# Yitran_IT900_Hutschiene_PIM7A_908_1_4_un.net
KiCad netlist of a schematic drawn in EAGLE
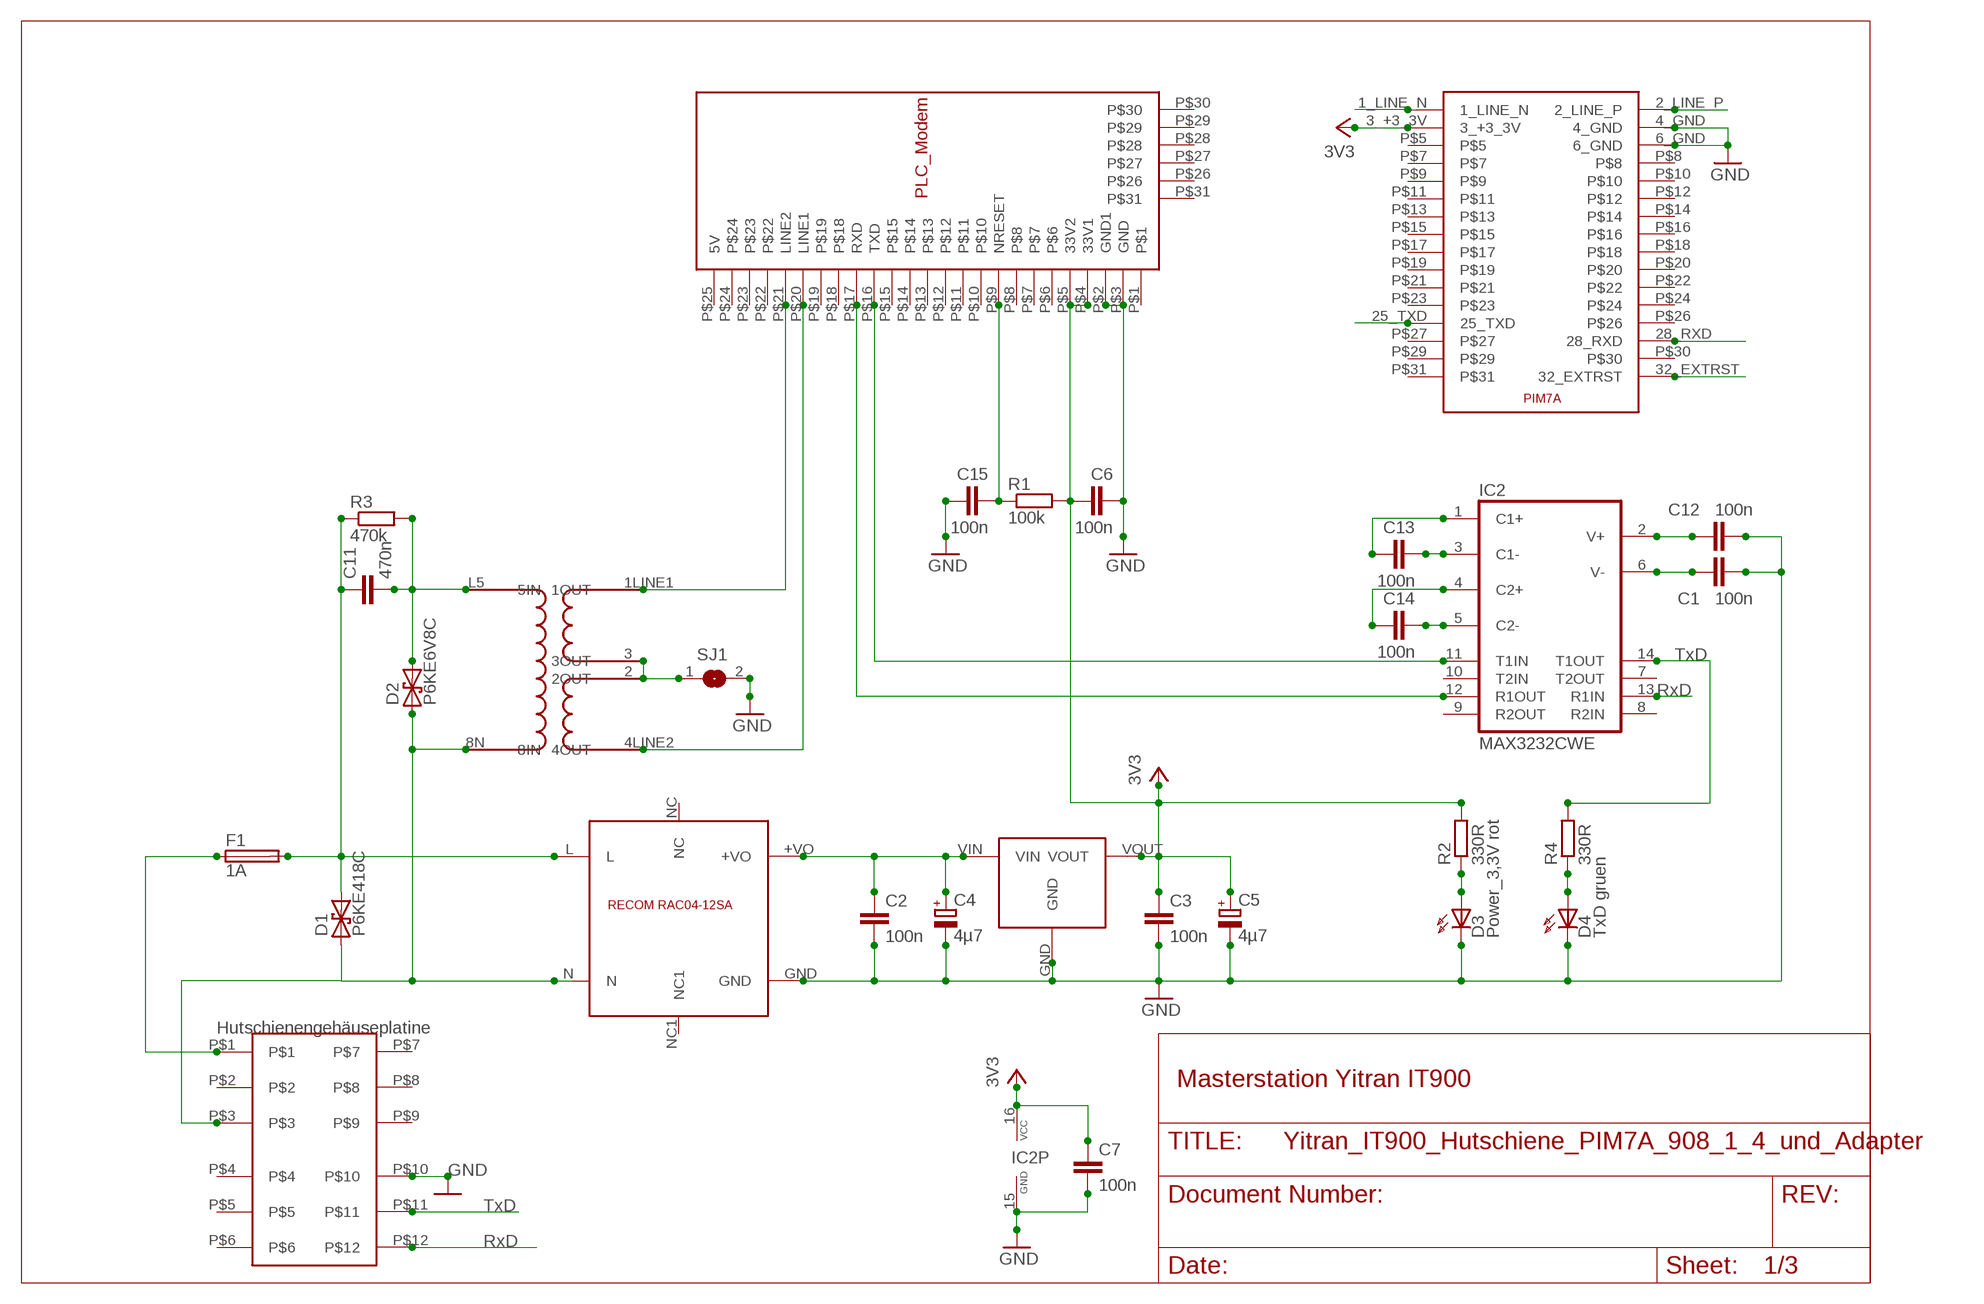
[diagram p0: schematic, sheet 1]
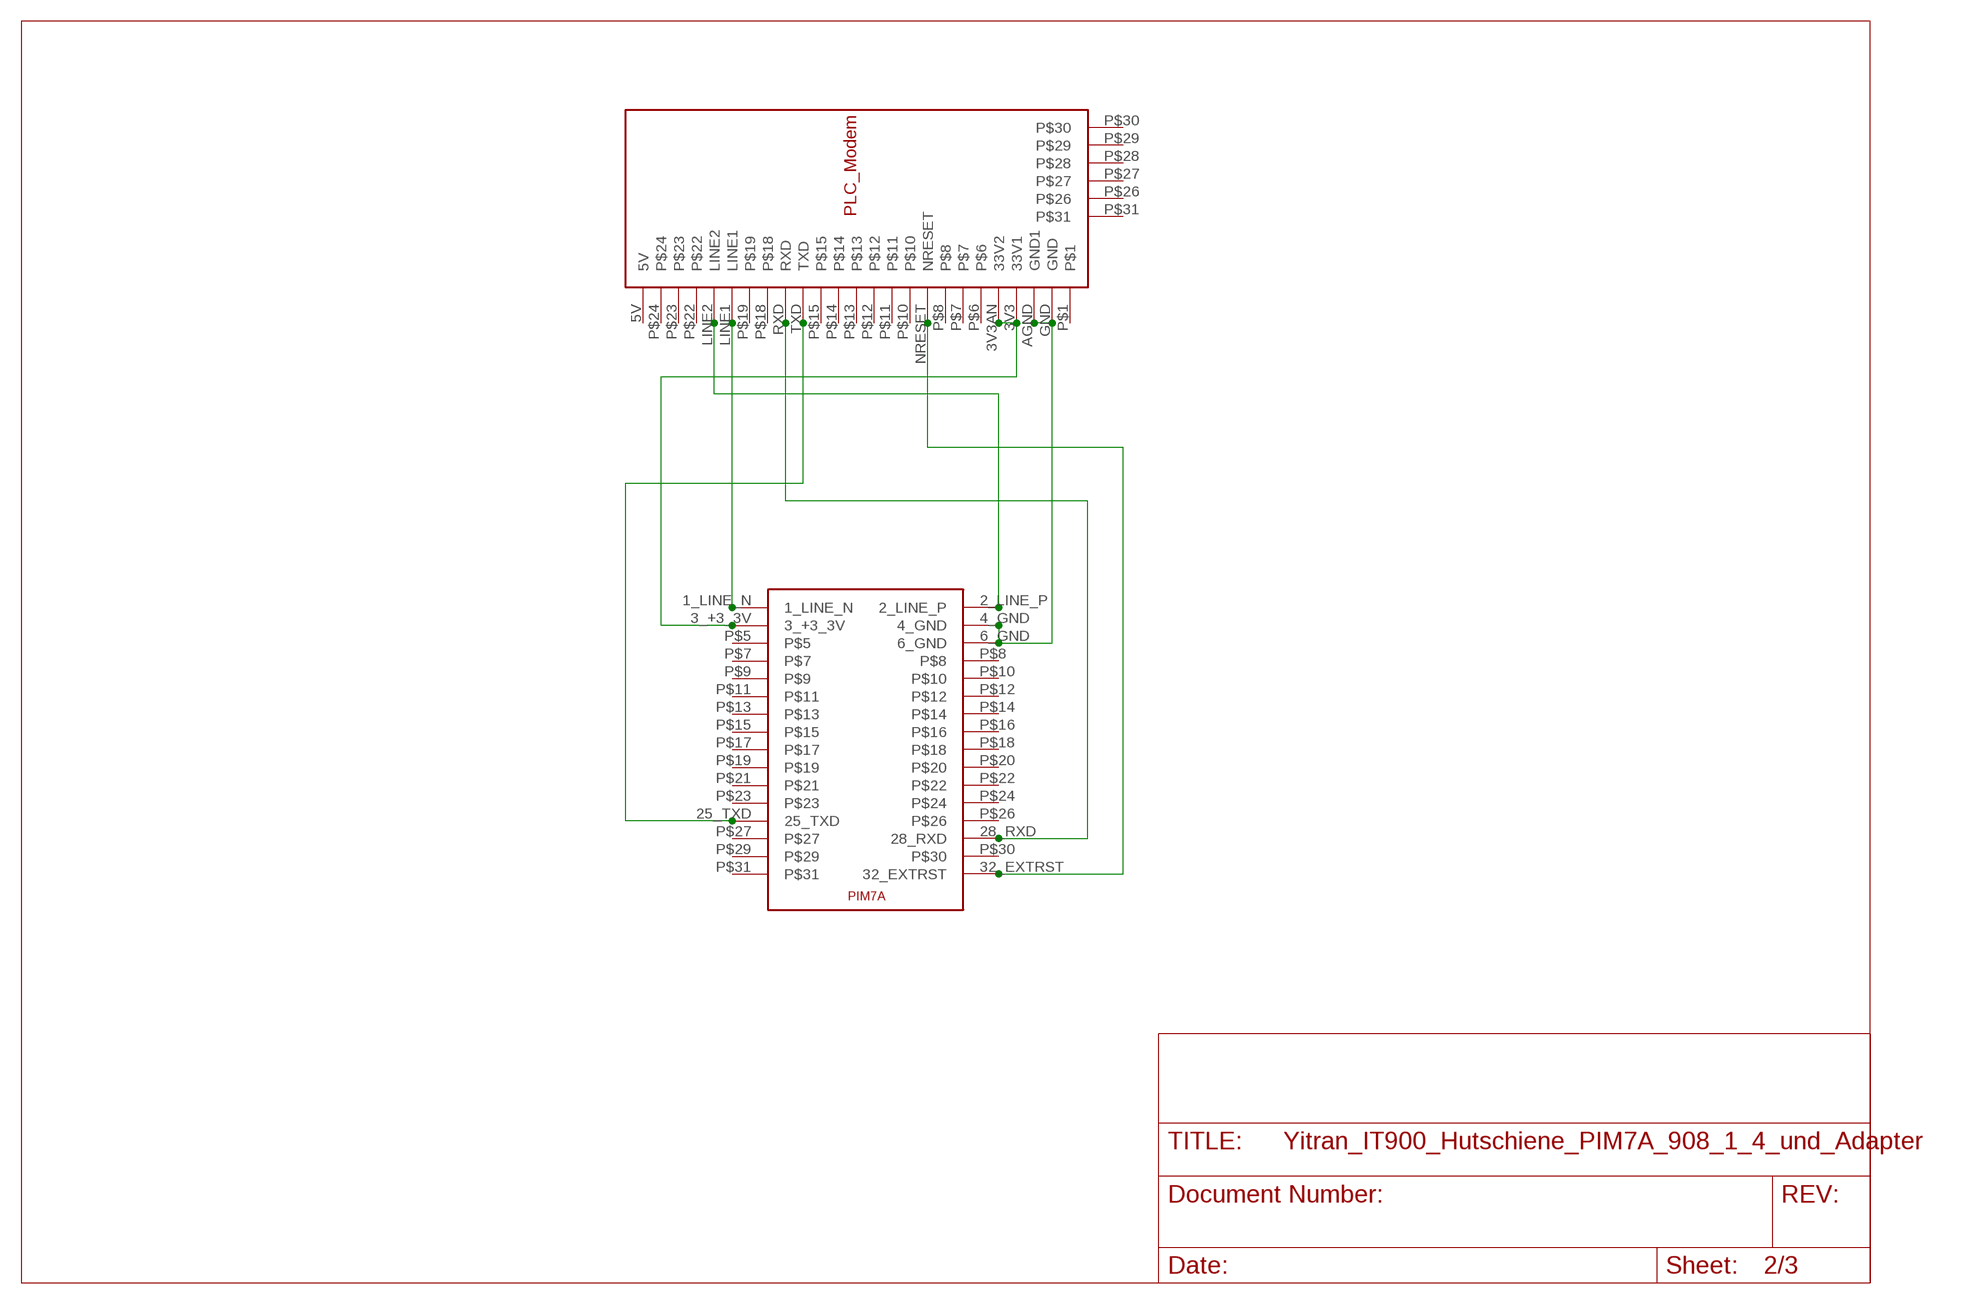
[diagram p1: schematic, sheet 2]
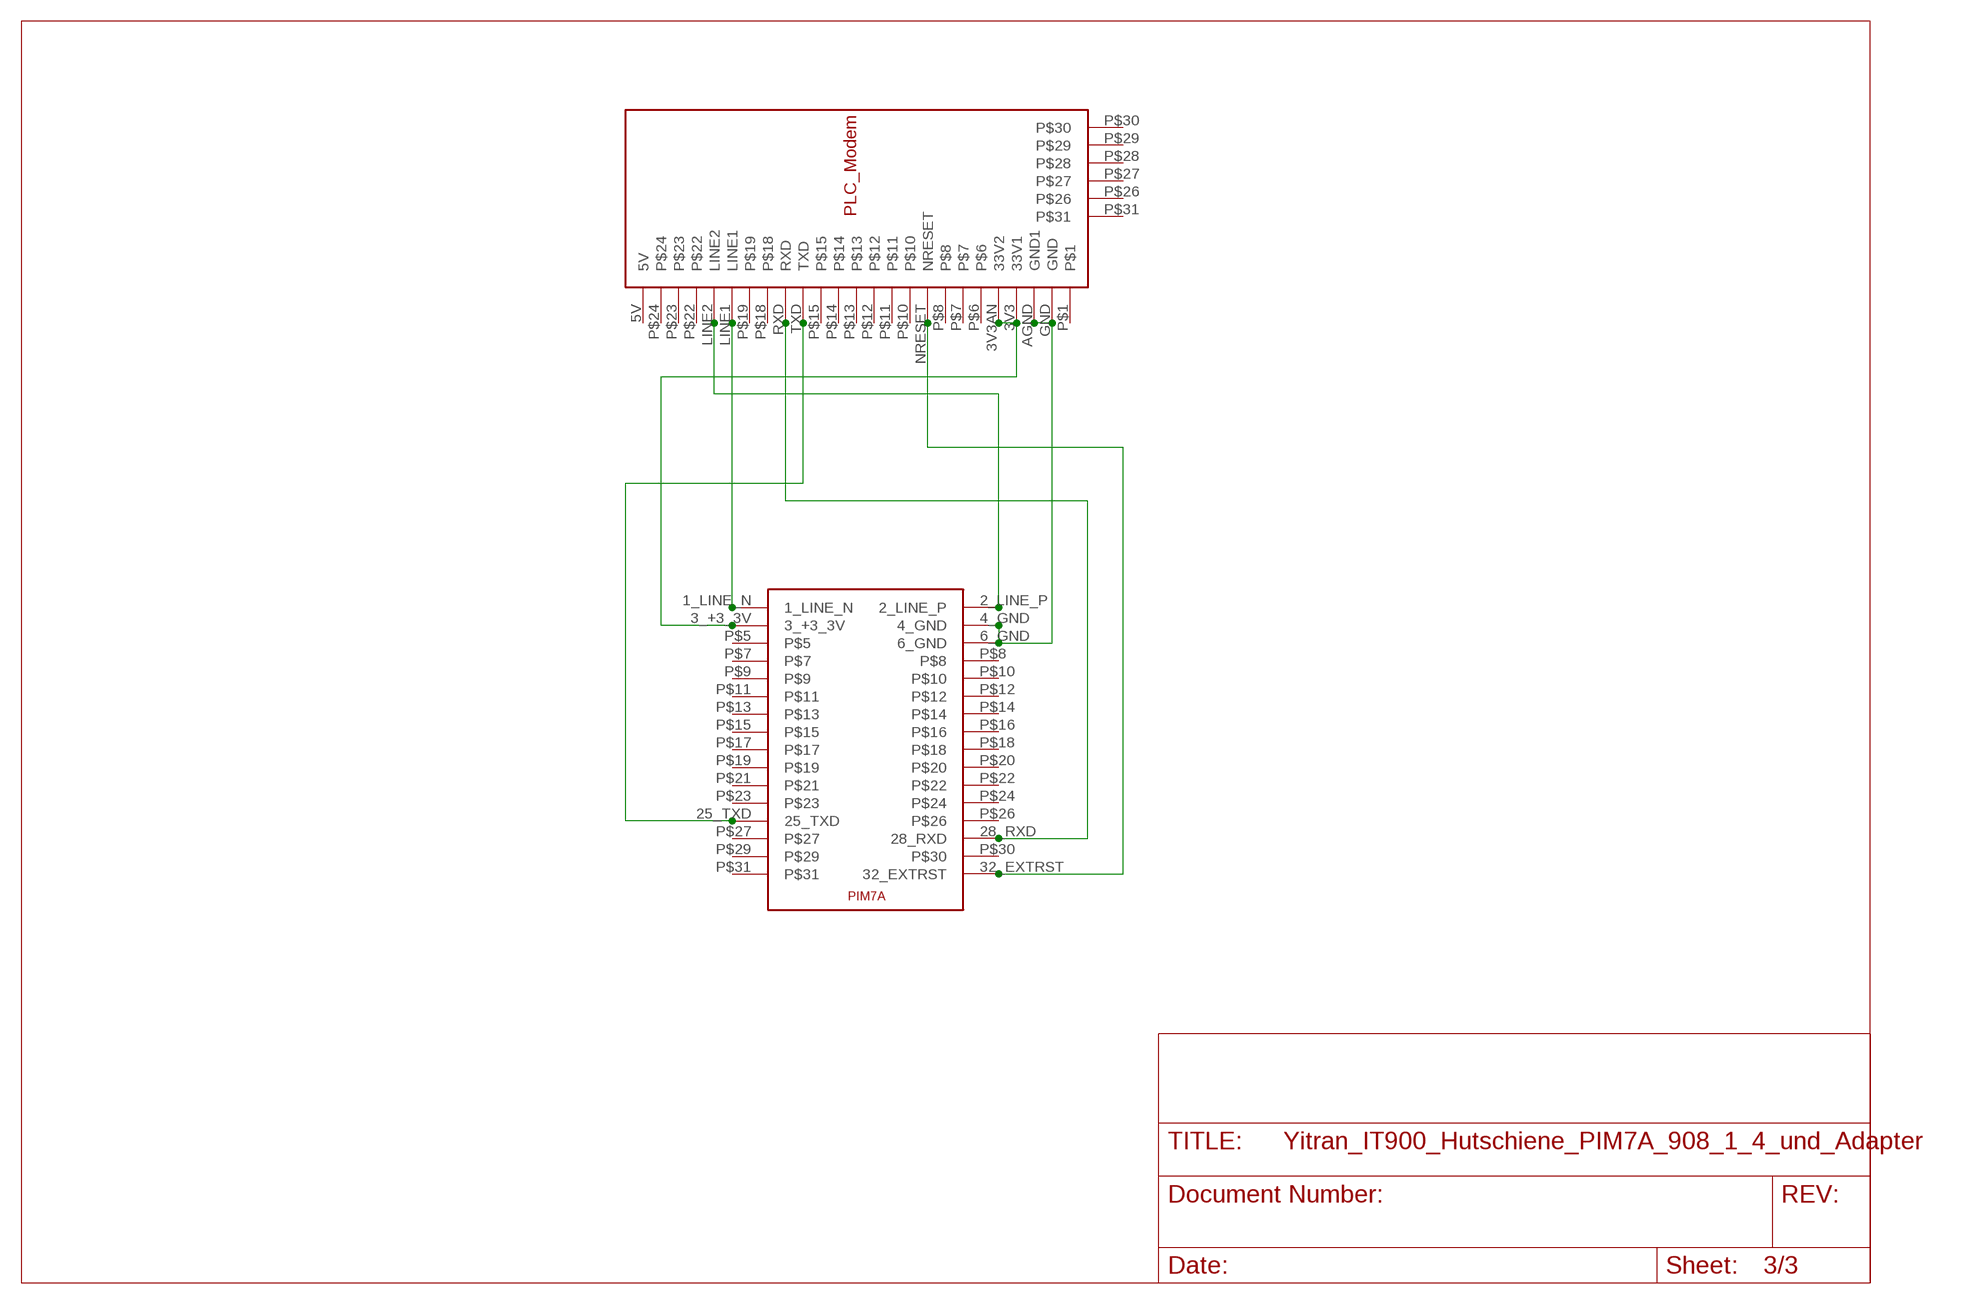
[diagram p2: schematic, sheet 3]

(export (version "E")
  (design (tool "Eeschema 10.0.6"))
  (components
    (comp (ref "U$5")
      (value "MODEMSTECKER_KLEINE_PINS")
      (footprint "eagle-import:MODEM_FUSS_KLEINE_PINS")
      (libsource (lib "eagle-import") (part "MODEMSTECKER_KLEINE_PINS"))
    )
    (comp (ref "U$6")
      (value "IT900PIM7A")
      (footprint "eagle-import:IT900PIM7A")
      (libsource (lib "eagle-import") (part "IT900PIM7A"))
    )
    (comp (ref "U$7")
      (value "MODEMSTECKER_KLEINE_PINS")
      (footprint "eagle-import:MODEM_FUSS_KLEINE_PINS")
      (libsource (lib "eagle-import") (part "MODEMSTECKER_KLEINE_PINS"))
    )
    (comp (ref "U$8")
      (value "IT900PIM7A")
      (footprint "eagle-import:IT900PIM7A")
      (libsource (lib "eagle-import") (part "IT900PIM7A"))
    )
    (comp (ref "C1")
      (value "100n")
      (footprint "eagle-import:C1206K")
      (libsource (lib "eagle-import") (part "C-EUC1206K"))
    )
    (comp (ref "C2")
      (value "100n")
      (footprint "eagle-import:C1206K")
      (libsource (lib "eagle-import") (part "C-EUC1206K"))
    )
    (comp (ref "C3")
      (value "100n")
      (footprint "eagle-import:C1206K")
      (libsource (lib "eagle-import") (part "C-EUC1206K"))
    )
    (comp (ref "C4")
      (value "4µ7")
      (footprint "eagle-import:E2,5-5")
      (libsource (lib "eagle-import") (part "CPOL-EUE2.5-5"))
    )
    (comp (ref "C5")
      (value "4µ7")
      (footprint "eagle-import:E2,5-5")
      (libsource (lib "eagle-import") (part "CPOL-EUE2.5-5"))
    )
    (comp (ref "C6")
      (value "100n")
      (footprint "eagle-import:C1206K")
      (libsource (lib "eagle-import") (part "C-EUC1206K"))
    )
    (comp (ref "C7")
      (value "100n")
      (footprint "eagle-import:C1206K")
      (libsource (lib "eagle-import") (part "C-EUC1206K"))
    )
    (comp (ref "C11")
      (value "470n")
      (footprint "eagle-import:C150-091X182")
      (libsource (lib "eagle-import") (part "C-EU150-091X182"))
    )
    (comp (ref "C12")
      (value "100n")
      (footprint "eagle-import:C1206K")
      (libsource (lib "eagle-import") (part "C-EUC1206K"))
    )
    (comp (ref "C13")
      (value "100n")
      (footprint "eagle-import:C1206K")
      (libsource (lib "eagle-import") (part "C-EUC1206K"))
    )
    (comp (ref "C14")
      (value "100n")
      (footprint "eagle-import:C1206K")
      (libsource (lib "eagle-import") (part "C-EUC1206K"))
    )
    (comp (ref "C15")
      (value "100n")
      (footprint "eagle-import:C1206K")
      (libsource (lib "eagle-import") (part "C-EUC1206K"))
    )
    (comp (ref "D1")
      (value "P6KE418C")
      (footprint "eagle-import:CB417-15")
      (libsource (lib "eagle-import") (part "P6KEXXC"))
    )
    (comp (ref "D2")
      (value "P6KE6V8C")
      (footprint "eagle-import:CB417-15")
      (libsource (lib "eagle-import") (part "P6KEXXC"))
    )
    (comp (ref "D3")
      (value "Power_3,3V rot")
      (footprint "eagle-import:HLMP6")
      (fields (field (name "MF") "AGILENT TECHNOLOGIES") (field (name "MPN") "HLMP-6500"))
      (libsource (lib "eagle-import") (part "HLMP6"))
    )
    (comp (ref "D4")
      (value "TxD gruen")
      (footprint "eagle-import:HLMP6")
      (fields (field (name "MF") "AGILENT TECHNOLOGIES") (field (name "MPN") "HLMP-6500"))
      (libsource (lib "eagle-import") (part "HLMP6"))
    )
    (comp (ref "F1")
      (value "1A")
      (footprint "eagle-import:TR5")
      (libsource (lib "eagle-import") (part "TR5"))
    )
    (comp (ref "IC2")
      (value "MAX3232CWE")
      (footprint "eagle-import:SO16L")
      (fields (field (name "MF") "MAXIM") (field (name "MPN") "MAX3232CWE+"))
      (libsource (lib "eagle-import") (part "MAX3232WEC"))
    )
    (comp (ref "R1")
      (value "100k")
      (footprint "eagle-import:M1406")
      (libsource (lib "eagle-import") (part "R-EU_M1406"))
    )
    (comp (ref "R2")
      (value "330R")
      (footprint "eagle-import:R1206")
      (libsource (lib "eagle-import") (part "R-EU_R1206"))
    )
    (comp (ref "R3")
      (value "470k")
      (footprint "eagle-import:0309_10")
      (libsource (lib "eagle-import") (part "R-EU_0309/10"))
    )
    (comp (ref "R4")
      (value "330R")
      (footprint "eagle-import:R1206")
      (libsource (lib "eagle-import") (part "R-EU_R1206"))
    )
    (comp (ref "SJ1")
      (value "SJW")
      (footprint "eagle-import:SJW")
      (libsource (lib "eagle-import") (part "SJW"))
    )
    (comp (ref "U$1")
      (value "RECOM_783_3")
      (footprint "eagle-import:RECOM785X")
      (libsource (lib "eagle-import") (part "RECOM_785_05"))
    )
    (comp (ref "U$2")
      (value "LDG-A-12")
      (footprint "eagle-import:LDG-A-12")
      (libsource (lib "eagle-import") (part "LDG-A-12"))
    )
    (comp (ref "U$3")
      (value "MODEMSTECKER")
      (footprint "eagle-import:MODEM_FUSS")
      (libsource (lib "eagle-import") (part "MODEMSTECKER"))
    )
    (comp (ref "U$4")
      (value "IT900PIM7A")
      (footprint "eagle-import:IT900PIM7A")
      (libsource (lib "eagle-import") (part "IT900PIM7A"))
    )
    (comp (ref "U$9")
      (value "RECOM_RAC04_12SA")
      (footprint "eagle-import:RAC04_12SA")
      (libsource (lib "eagle-import") (part "RECOM_RAC04_12SA"))
    )
    (comp (ref "U$10")
      (value "PLC_UEBERTRAGER_V2")
      (footprint "eagle-import:PLC-UEBERTRAGER_V2")
      (libsource (lib "eagle-import") (part "PLC_UEBERTRAGER_V2"))
    )
  )
  (nets
    (net (code "1") (name "3V3") (class "Default")
      (node (ref "C3") (pin "1") (pinfunction "1_1") (pintype "passive"))
      (node (ref "C5") (pin "+") (pinfunction "+_+") (pintype "passive"))
      (node (ref "C6") (pin "1") (pinfunction "1_1") (pintype "passive"))
      (node (ref "C7") (pin "1") (pinfunction "1_1") (pintype "passive"))
      (node (ref "IC2") (pin "16") (pinfunction "VCC_16") (pintype "power_in"))
      (node (ref "R1") (pin "2") (pinfunction "2_2") (pintype "passive"))
      (node (ref "R2") (pin "2") (pinfunction "2_2") (pintype "passive"))
      (node (ref "U$1") (pin "VOUT") (pinfunction "VOUT_VOUT") (pintype "bidirectional"))
      (node (ref "U$3") (pin "P$4") (pinfunction "33V1_P$4") (pintype "bidirectional"))
      (node (ref "U$3") (pin "P$5") (pinfunction "33V2_P$5") (pintype "bidirectional"))
      (node (ref "U$4") (pin "3_+3_3V") (pinfunction "3_+3_3V_3_+3_3V") (pintype "bidirectional"))
    )
    (net (code "2") (name "EXTRST") (class "Default")
      (node (ref "C15") (pin "2") (pinfunction "2_2") (pintype "passive"))
      (node (ref "R1") (pin "1") (pinfunction "1_1") (pintype "passive"))
      (node (ref "U$3") (pin "P$9") (pinfunction "NRESET_P$9") (pintype "bidirectional"))
      (node (ref "U$4") (pin "32_EXTRST") (pinfunction "32_EXTRST_32_EXTRST") (pintype "bidirectional"))
    )
    (net (code "3") (name "GND") (class "Default")
      (node (ref "C1") (pin "2") (pinfunction "2_2") (pintype "passive"))
      (node (ref "C12") (pin "2") (pinfunction "2_2") (pintype "passive"))
      (node (ref "C15") (pin "1") (pinfunction "1_1") (pintype "passive"))
      (node (ref "C2") (pin "2") (pinfunction "2_2") (pintype "passive"))
      (node (ref "C3") (pin "2") (pinfunction "2_2") (pintype "passive"))
      (node (ref "C4") (pin "-") (pinfunction "-_-") (pintype "passive"))
      (node (ref "C5") (pin "-") (pinfunction "-_-") (pintype "passive"))
      (node (ref "C6") (pin "2") (pinfunction "2_2") (pintype "passive"))
      (node (ref "C7") (pin "2") (pinfunction "2_2") (pintype "passive"))
      (node (ref "D3") (pin "K") (pinfunction "K_K") (pintype "passive"))
      (node (ref "D4") (pin "K") (pinfunction "K_K") (pintype "passive"))
      (node (ref "IC2") (pin "15") (pinfunction "GND_15") (pintype "power_in"))
      (node (ref "SJ1") (pin "2") (pinfunction "2_2") (pintype "passive"))
      (node (ref "U$1") (pin "GND") (pinfunction "GND_GND") (pintype "bidirectional"))
      (node (ref "U$2") (pin "P$10") (pinfunction "P$10_P$10") (pintype "bidirectional"))
      (node (ref "U$3") (pin "P$2") (pinfunction "GND1_P$2") (pintype "bidirectional"))
      (node (ref "U$3") (pin "P$3") (pinfunction "GND_P$3") (pintype "bidirectional"))
      (node (ref "U$4") (pin "4_GND") (pinfunction "4_GND_4_GND") (pintype "bidirectional"))
      (node (ref "U$4") (pin "6_GND") (pinfunction "6_GND_6_GND") (pintype "bidirectional"))
      (node (ref "U$9") (pin "GND") (pinfunction "GND_GND") (pintype "bidirectional"))
    )
    (net (code "4") (name "LINE1") (class "Default")
      (node (ref "U$10") (pin "4LINE2") (pinfunction "4OUT_4LINE2") (pintype "output"))
      (node (ref "U$3") (pin "P$20") (pinfunction "LINE1_P$20") (pintype "bidirectional"))
      (node (ref "U$4") (pin "1_LINE_N") (pinfunction "1_LINE_N_1_LINE_N") (pintype "bidirectional"))
    )
    (net (code "5") (name "LINE2") (class "Default")
      (node (ref "U$10") (pin "1LINE1") (pinfunction "1OUT_1LINE1") (pintype "output"))
      (node (ref "U$3") (pin "P$21") (pinfunction "LINE2_P$21") (pintype "bidirectional"))
      (node (ref "U$4") (pin "2_LINE_P") (pinfunction "2_LINE_P_2_LINE_P") (pintype "bidirectional"))
    )
    (net (code "6") (name "Net-(C2-Pad1)") (class "Default")
      (node (ref "C2") (pin "1") (pinfunction "1_1") (pintype "passive"))
      (node (ref "C4") (pin "+") (pinfunction "+_+") (pintype "passive"))
      (node (ref "U$1") (pin "VIN") (pinfunction "VIN_VIN") (pintype "bidirectional"))
      (node (ref "U$9") (pin "+VO") (pinfunction "+VO_+VO") (pintype "bidirectional"))
    )
    (net (code "7") (name "Net-(D1-1)") (class "Default")
      (node (ref "D1") (pin "A") (pinfunction "1_A") (pintype "passive"))
      (node (ref "D2") (pin "A") (pinfunction "1_A") (pintype "passive"))
      (node (ref "U$10") (pin "8N") (pinfunction "8IN_8N") (pintype "input"))
      (node (ref "U$2") (pin "P$3") (pinfunction "P$3_P$3") (pintype "bidirectional"))
      (node (ref "U$9") (pin "N") (pinfunction "N_N") (pintype "bidirectional"))
    )
    (net (code "8") (name "Net-(D1-2)") (class "Default")
      (node (ref "C11") (pin "1") (pinfunction "1_1") (pintype "passive"))
      (node (ref "D1") (pin "C") (pinfunction "2_C") (pintype "passive"))
      (node (ref "F1") (pin "2") (pinfunction "2_2") (pintype "passive"))
      (node (ref "R3") (pin "1") (pinfunction "1_1") (pintype "passive"))
      (node (ref "U$9") (pin "L") (pinfunction "L_L") (pintype "bidirectional"))
    )
    (net (code "9") (name "Net-(D2-2)") (class "Default")
      (node (ref "C11") (pin "2") (pinfunction "2_2") (pintype "passive"))
      (node (ref "D2") (pin "C") (pinfunction "2_C") (pintype "passive"))
      (node (ref "R3") (pin "2") (pinfunction "2_2") (pintype "passive"))
      (node (ref "U$10") (pin "L5") (pinfunction "5IN_L5") (pintype "input"))
    )
    (net (code "10") (name "Net-(D3-PadA)") (class "Default")
      (node (ref "D3") (pin "A") (pinfunction "A_A") (pintype "passive"))
      (node (ref "R2") (pin "1") (pinfunction "1_1") (pintype "passive"))
    )
    (net (code "11") (name "Net-(D4-PadA)") (class "Default")
      (node (ref "D4") (pin "A") (pinfunction "A_A") (pintype "passive"))
      (node (ref "R4") (pin "1") (pinfunction "1_1") (pintype "passive"))
    )
    (net (code "12") (name "Net-(F1-Pad1)") (class "Default")
      (node (ref "F1") (pin "1") (pinfunction "1_1") (pintype "passive"))
      (node (ref "U$2") (pin "P$1") (pinfunction "P$1_P$1") (pintype "bidirectional"))
    )
    (net (code "13") (name "Net-(IC2A-C1+)") (class "Default")
      (node (ref "C13") (pin "1") (pinfunction "1_1") (pintype "passive"))
      (node (ref "IC2") (pin "1") (pinfunction "C1+_1") (pintype "bidirectional"))
    )
    (net (code "14") (name "Net-(IC2A-C1-)") (class "Default")
      (node (ref "C13") (pin "2") (pinfunction "2_2") (pintype "passive"))
      (node (ref "IC2") (pin "3") (pinfunction "C1-_3") (pintype "bidirectional"))
    )
    (net (code "15") (name "Net-(IC2A-C2+)") (class "Default")
      (node (ref "C14") (pin "1") (pinfunction "1_1") (pintype "passive"))
      (node (ref "IC2") (pin "4") (pinfunction "C2+_4") (pintype "bidirectional"))
    )
    (net (code "16") (name "Net-(IC2A-C2-)") (class "Default")
      (node (ref "C14") (pin "2") (pinfunction "2_2") (pintype "passive"))
      (node (ref "IC2") (pin "5") (pinfunction "C2-_5") (pintype "bidirectional"))
    )
    (net (code "17") (name "Net-(IC2A-V+)") (class "Default")
      (node (ref "C12") (pin "1") (pinfunction "1_1") (pintype "passive"))
      (node (ref "IC2") (pin "2") (pinfunction "V+_2") (pintype "bidirectional"))
    )
    (net (code "18") (name "Net-(IC2A-V-)") (class "Default")
      (node (ref "C1") (pin "1") (pinfunction "1_1") (pintype "passive"))
      (node (ref "IC2") (pin "6") (pinfunction "V-_6") (pintype "bidirectional"))
    )
    (net (code "19") (name "Net-(U$5-33V1)") (class "Default")
      (node (ref "U$5") (pin "3V3") (pinfunction "33V1_3V3") (pintype "bidirectional"))
      (node (ref "U$5") (pin "3V3AN") (pinfunction "33V2_3V3AN") (pintype "bidirectional"))
      (node (ref "U$6") (pin "3_+3_3V") (pinfunction "3_+3_3V_3_+3_3V") (pintype "bidirectional"))
    )
    (net (code "20") (name "Net-(U$5-GND1)") (class "Default")
      (node (ref "U$5") (pin "AGND") (pinfunction "GND1_AGND") (pintype "bidirectional"))
      (node (ref "U$5") (pin "GND") (pinfunction "GND_GND") (pintype "bidirectional"))
      (node (ref "U$6") (pin "4_GND") (pinfunction "4_GND_4_GND") (pintype "bidirectional"))
      (node (ref "U$6") (pin "6_GND") (pinfunction "6_GND_6_GND") (pintype "bidirectional"))
    )
    (net (code "21") (name "Net-(U$5-PadLINE1)") (class "Default")
      (node (ref "U$5") (pin "LINE1") (pinfunction "LINE1_LINE1") (pintype "bidirectional"))
      (node (ref "U$6") (pin "1_LINE_N") (pinfunction "1_LINE_N_1_LINE_N") (pintype "bidirectional"))
    )
    (net (code "22") (name "Net-(U$5-PadLINE2)") (class "Default")
      (node (ref "U$5") (pin "LINE2") (pinfunction "LINE2_LINE2") (pintype "bidirectional"))
      (node (ref "U$6") (pin "2_LINE_P") (pinfunction "2_LINE_P_2_LINE_P") (pintype "bidirectional"))
    )
    (net (code "23") (name "Net-(U$5-PadNRESET)") (class "Default")
      (node (ref "U$5") (pin "NRESET") (pinfunction "NRESET_NRESET") (pintype "bidirectional"))
      (node (ref "U$6") (pin "32_EXTRST") (pinfunction "32_EXTRST_32_EXTRST") (pintype "bidirectional"))
    )
    (net (code "24") (name "Net-(U$5-PadRXD)") (class "Default")
      (node (ref "U$5") (pin "RXD") (pinfunction "RXD_RXD") (pintype "bidirectional"))
      (node (ref "U$6") (pin "28_RXD") (pinfunction "28_RXD_28_RXD") (pintype "bidirectional"))
    )
    (net (code "25") (name "Net-(U$5-PadTXD)") (class "Default")
      (node (ref "U$5") (pin "TXD") (pinfunction "TXD_TXD") (pintype "bidirectional"))
      (node (ref "U$6") (pin "25_TXD") (pinfunction "25_TXD_25_TXD") (pintype "bidirectional"))
    )
    (net (code "26") (name "Net-(U$7-33V1)") (class "Default")
      (node (ref "U$7") (pin "3V3") (pinfunction "33V1_3V3") (pintype "bidirectional"))
      (node (ref "U$7") (pin "3V3AN") (pinfunction "33V2_3V3AN") (pintype "bidirectional"))
      (node (ref "U$8") (pin "3_+3_3V") (pinfunction "3_+3_3V_3_+3_3V") (pintype "bidirectional"))
    )
    (net (code "27") (name "Net-(U$7-GND1)") (class "Default")
      (node (ref "U$7") (pin "AGND") (pinfunction "GND1_AGND") (pintype "bidirectional"))
      (node (ref "U$7") (pin "GND") (pinfunction "GND_GND") (pintype "bidirectional"))
      (node (ref "U$8") (pin "4_GND") (pinfunction "4_GND_4_GND") (pintype "bidirectional"))
      (node (ref "U$8") (pin "6_GND") (pinfunction "6_GND_6_GND") (pintype "bidirectional"))
    )
    (net (code "28") (name "Net-(U$7-PadLINE1)") (class "Default")
      (node (ref "U$7") (pin "LINE1") (pinfunction "LINE1_LINE1") (pintype "bidirectional"))
      (node (ref "U$8") (pin "1_LINE_N") (pinfunction "1_LINE_N_1_LINE_N") (pintype "bidirectional"))
    )
    (net (code "29") (name "Net-(U$7-PadLINE2)") (class "Default")
      (node (ref "U$7") (pin "LINE2") (pinfunction "LINE2_LINE2") (pintype "bidirectional"))
      (node (ref "U$8") (pin "2_LINE_P") (pinfunction "2_LINE_P_2_LINE_P") (pintype "bidirectional"))
    )
    (net (code "30") (name "Net-(U$7-PadNRESET)") (class "Default")
      (node (ref "U$7") (pin "NRESET") (pinfunction "NRESET_NRESET") (pintype "bidirectional"))
      (node (ref "U$8") (pin "32_EXTRST") (pinfunction "32_EXTRST_32_EXTRST") (pintype "bidirectional"))
    )
    (net (code "31") (name "Net-(U$7-PadRXD)") (class "Default")
      (node (ref "U$7") (pin "RXD") (pinfunction "RXD_RXD") (pintype "bidirectional"))
      (node (ref "U$8") (pin "28_RXD") (pinfunction "28_RXD_28_RXD") (pintype "bidirectional"))
    )
    (net (code "32") (name "Net-(U$7-PadTXD)") (class "Default")
      (node (ref "U$7") (pin "TXD") (pinfunction "TXD_TXD") (pintype "bidirectional"))
      (node (ref "U$8") (pin "25_TXD") (pinfunction "25_TXD_25_TXD") (pintype "bidirectional"))
    )
    (net (code "33") (name "Net-(U$10-2OUT)") (class "Default")
      (node (ref "SJ1") (pin "1") (pinfunction "1_1") (pintype "passive"))
      (node (ref "U$10") (pin "2") (pinfunction "2OUT_2") (pintype "output"))
      (node (ref "U$10") (pin "3") (pinfunction "3OUT_3") (pintype "output"))
    )
    (net (code "34") (name "RX") (class "Default")
      (node (ref "IC2") (pin "12") (pinfunction "R1OUT_12") (pintype "output"))
      (node (ref "U$3") (pin "P$17") (pinfunction "RXD_P$17") (pintype "bidirectional"))
      (node (ref "U$4") (pin "28_RXD") (pinfunction "28_RXD_28_RXD") (pintype "bidirectional"))
    )
    (net (code "35") (name "RXD") (class "Default")
      (node (ref "IC2") (pin "13") (pinfunction "R1IN_13") (pintype "input"))
      (node (ref "U$2") (pin "P$12") (pinfunction "P$12_P$12") (pintype "bidirectional"))
    )
    (net (code "36") (name "TX") (class "Default")
      (node (ref "IC2") (pin "11") (pinfunction "T1IN_11") (pintype "input"))
      (node (ref "U$3") (pin "P$16") (pinfunction "TXD_P$16") (pintype "bidirectional"))
      (node (ref "U$4") (pin "25_TXD") (pinfunction "25_TXD_25_TXD") (pintype "bidirectional"))
    )
    (net (code "37") (name "TXD") (class "Default")
      (node (ref "IC2") (pin "14") (pinfunction "T1OUT_14") (pintype "output"))
      (node (ref "R4") (pin "2") (pinfunction "2_2") (pintype "passive"))
      (node (ref "U$2") (pin "P$11") (pinfunction "P$11_P$11") (pintype "bidirectional"))
    )
    (net (code "38") (name "unconnected-(IC2A-R2IN-Pad8)") (class "Default")
      (node (ref "IC2") (pin "8") (pinfunction "R2IN_8") (pintype "input"))
    )
    (net (code "39") (name "unconnected-(IC2A-R2OUT-Pad9)") (class "Default")
      (node (ref "IC2") (pin "9") (pinfunction "R2OUT_9") (pintype "output"))
    )
    (net (code "40") (name "unconnected-(IC2A-T2IN-Pad10)") (class "Default")
      (node (ref "IC2") (pin "10") (pinfunction "T2IN_10") (pintype "input"))
    )
    (net (code "41") (name "unconnected-(IC2A-T2OUT-Pad7)") (class "Default")
      (node (ref "IC2") (pin "7") (pinfunction "T2OUT_7") (pintype "output"))
    )
    (net (code "42") (name "unconnected-(U$2-PadP$2)") (class "Default")
      (node (ref "U$2") (pin "P$2") (pinfunction "P$2_P$2") (pintype "bidirectional"))
    )
    (net (code "43") (name "unconnected-(U$2-PadP$4)") (class "Default")
      (node (ref "U$2") (pin "P$4") (pinfunction "P$4_P$4") (pintype "bidirectional"))
    )
    (net (code "44") (name "unconnected-(U$2-PadP$5)") (class "Default")
      (node (ref "U$2") (pin "P$5") (pinfunction "P$5_P$5") (pintype "bidirectional"))
    )
    (net (code "45") (name "unconnected-(U$2-PadP$6)") (class "Default")
      (node (ref "U$2") (pin "P$6") (pinfunction "P$6_P$6") (pintype "bidirectional"))
    )
    (net (code "46") (name "unconnected-(U$2-PadP$7)") (class "Default")
      (node (ref "U$2") (pin "P$7") (pinfunction "P$7_P$7") (pintype "bidirectional"))
    )
    (net (code "47") (name "unconnected-(U$2-PadP$8)") (class "Default")
      (node (ref "U$2") (pin "P$8") (pinfunction "P$8_P$8") (pintype "bidirectional"))
    )
    (net (code "48") (name "unconnected-(U$2-PadP$9)") (class "Default")
      (node (ref "U$2") (pin "P$9") (pinfunction "P$9_P$9") (pintype "bidirectional"))
    )
    (net (code "49") (name "unconnected-(U$3-5V-PadP$25)") (class "Default")
      (node (ref "U$3") (pin "P$25") (pinfunction "5V_P$25") (pintype "bidirectional"))
    )
    (net (code "50") (name "unconnected-(U$3-PadP$1)") (class "Default")
      (node (ref "U$3") (pin "P$1") (pinfunction "P$1_P$1") (pintype "bidirectional"))
    )
    (net (code "51") (name "unconnected-(U$3-PadP$6)") (class "Default")
      (node (ref "U$3") (pin "P$6") (pinfunction "P$6_P$6") (pintype "bidirectional"))
    )
    (net (code "52") (name "unconnected-(U$3-PadP$7)") (class "Default")
      (node (ref "U$3") (pin "P$7") (pinfunction "P$7_P$7") (pintype "bidirectional"))
    )
    (net (code "53") (name "unconnected-(U$3-PadP$8)") (class "Default")
      (node (ref "U$3") (pin "P$8") (pinfunction "P$8_P$8") (pintype "bidirectional"))
    )
    (net (code "54") (name "unconnected-(U$3-PadP$10)") (class "Default")
      (node (ref "U$3") (pin "P$10") (pinfunction "P$10_P$10") (pintype "bidirectional"))
    )
    (net (code "55") (name "unconnected-(U$3-PadP$11)") (class "Default")
      (node (ref "U$3") (pin "P$11") (pinfunction "P$11_P$11") (pintype "bidirectional"))
    )
    (net (code "56") (name "unconnected-(U$3-PadP$12)") (class "Default")
      (node (ref "U$3") (pin "P$12") (pinfunction "P$12_P$12") (pintype "bidirectional"))
    )
    (net (code "57") (name "unconnected-(U$3-PadP$13)") (class "Default")
      (node (ref "U$3") (pin "P$13") (pinfunction "P$13_P$13") (pintype "bidirectional"))
    )
    (net (code "58") (name "unconnected-(U$3-PadP$14)") (class "Default")
      (node (ref "U$3") (pin "P$14") (pinfunction "P$14_P$14") (pintype "bidirectional"))
    )
    (net (code "59") (name "unconnected-(U$3-PadP$15)") (class "Default")
      (node (ref "U$3") (pin "P$15") (pinfunction "P$15_P$15") (pintype "bidirectional"))
    )
    (net (code "60") (name "unconnected-(U$3-PadP$18)") (class "Default")
      (node (ref "U$3") (pin "P$18") (pinfunction "P$18_P$18") (pintype "bidirectional"))
    )
    (net (code "61") (name "unconnected-(U$3-PadP$19)") (class "Default")
      (node (ref "U$3") (pin "P$19") (pinfunction "P$19_P$19") (pintype "bidirectional"))
    )
    (net (code "62") (name "unconnected-(U$3-PadP$22)") (class "Default")
      (node (ref "U$3") (pin "P$22") (pinfunction "P$22_P$22") (pintype "bidirectional"))
    )
    (net (code "63") (name "unconnected-(U$3-PadP$23)") (class "Default")
      (node (ref "U$3") (pin "P$23") (pinfunction "P$23_P$23") (pintype "bidirectional"))
    )
    (net (code "64") (name "unconnected-(U$3-PadP$24)") (class "Default")
      (node (ref "U$3") (pin "P$24") (pinfunction "P$24_P$24") (pintype "bidirectional"))
    )
    (net (code "65") (name "unconnected-(U$3-PadP$26)") (class "Default")
      (node (ref "U$3") (pin "P$26") (pinfunction "P$26_P$26") (pintype "bidirectional"))
    )
    (net (code "66") (name "unconnected-(U$3-PadP$27)") (class "Default")
      (node (ref "U$3") (pin "P$27") (pinfunction "P$27_P$27") (pintype "bidirectional"))
    )
    (net (code "67") (name "unconnected-(U$3-PadP$28)") (class "Default")
      (node (ref "U$3") (pin "P$28") (pinfunction "P$28_P$28") (pintype "bidirectional"))
    )
    (net (code "68") (name "unconnected-(U$3-PadP$29)") (class "Default")
      (node (ref "U$3") (pin "P$29") (pinfunction "P$29_P$29") (pintype "bidirectional"))
    )
    (net (code "69") (name "unconnected-(U$3-PadP$30)") (class "Default")
      (node (ref "U$3") (pin "P$30") (pinfunction "P$30_P$30") (pintype "bidirectional"))
    )
    (net (code "70") (name "unconnected-(U$3-PadP$31)") (class "Default")
      (node (ref "U$3") (pin "P$31") (pinfunction "P$31_P$31") (pintype "bidirectional"))
    )
    (net (code "71") (name "unconnected-(U$4-PadP$5)") (class "Default")
      (node (ref "U$4") (pin "P$5") (pinfunction "P$5_P$5") (pintype "bidirectional"))
    )
    (net (code "72") (name "unconnected-(U$4-PadP$7)") (class "Default")
      (node (ref "U$4") (pin "P$7") (pinfunction "P$7_P$7") (pintype "bidirectional"))
    )
    (net (code "73") (name "unconnected-(U$4-PadP$8)") (class "Default")
      (node (ref "U$4") (pin "P$8") (pinfunction "P$8_P$8") (pintype "bidirectional"))
    )
    (net (code "74") (name "unconnected-(U$4-PadP$9)") (class "Default")
      (node (ref "U$4") (pin "P$9") (pinfunction "P$9_P$9") (pintype "bidirectional"))
    )
    (net (code "75") (name "unconnected-(U$4-PadP$10)") (class "Default")
      (node (ref "U$4") (pin "P$10") (pinfunction "P$10_P$10") (pintype "bidirectional"))
    )
    (net (code "76") (name "unconnected-(U$4-PadP$11)") (class "Default")
      (node (ref "U$4") (pin "P$11") (pinfunction "P$11_P$11") (pintype "bidirectional"))
    )
    (net (code "77") (name "unconnected-(U$4-PadP$12)") (class "Default")
      (node (ref "U$4") (pin "P$12") (pinfunction "P$12_P$12") (pintype "bidirectional"))
    )
    (net (code "78") (name "unconnected-(U$4-PadP$13)") (class "Default")
      (node (ref "U$4") (pin "P$13") (pinfunction "P$13_P$13") (pintype "bidirectional"))
    )
    (net (code "79") (name "unconnected-(U$4-PadP$14)") (class "Default")
      (node (ref "U$4") (pin "P$14") (pinfunction "P$14_P$14") (pintype "bidirectional"))
    )
    (net (code "80") (name "unconnected-(U$4-PadP$15)") (class "Default")
      (node (ref "U$4") (pin "P$15") (pinfunction "P$15_P$15") (pintype "bidirectional"))
    )
    (net (code "81") (name "unconnected-(U$4-PadP$16)") (class "Default")
      (node (ref "U$4") (pin "P$16") (pinfunction "P$16_P$16") (pintype "bidirectional"))
    )
    (net (code "82") (name "unconnected-(U$4-PadP$17)") (class "Default")
      (node (ref "U$4") (pin "P$17") (pinfunction "P$17_P$17") (pintype "bidirectional"))
    )
    (net (code "83") (name "unconnected-(U$4-PadP$18)") (class "Default")
      (node (ref "U$4") (pin "P$18") (pinfunction "P$18_P$18") (pintype "bidirectional"))
    )
    (net (code "84") (name "unconnected-(U$4-PadP$19)") (class "Default")
      (node (ref "U$4") (pin "P$19") (pinfunction "P$19_P$19") (pintype "bidirectional"))
    )
    (net (code "85") (name "unconnected-(U$4-PadP$20)") (class "Default")
      (node (ref "U$4") (pin "P$20") (pinfunction "P$20_P$20") (pintype "bidirectional"))
    )
    (net (code "86") (name "unconnected-(U$4-PadP$21)") (class "Default")
      (node (ref "U$4") (pin "P$21") (pinfunction "P$21_P$21") (pintype "bidirectional"))
    )
    (net (code "87") (name "unconnected-(U$4-PadP$22)") (class "Default")
      (node (ref "U$4") (pin "P$22") (pinfunction "P$22_P$22") (pintype "bidirectional"))
    )
    (net (code "88") (name "unconnected-(U$4-PadP$23)") (class "Default")
      (node (ref "U$4") (pin "P$23") (pinfunction "P$23_P$23") (pintype "bidirectional"))
    )
    (net (code "89") (name "unconnected-(U$4-PadP$24)") (class "Default")
      (node (ref "U$4") (pin "P$24") (pinfunction "P$24_P$24") (pintype "bidirectional"))
    )
    (net (code "90") (name "unconnected-(U$4-PadP$26)") (class "Default")
      (node (ref "U$4") (pin "P$26") (pinfunction "P$26_P$26") (pintype "bidirectional"))
    )
    (net (code "91") (name "unconnected-(U$4-PadP$27)") (class "Default")
      (node (ref "U$4") (pin "P$27") (pinfunction "P$27_P$27") (pintype "bidirectional"))
    )
    (net (code "92") (name "unconnected-(U$4-PadP$29)") (class "Default")
      (node (ref "U$4") (pin "P$29") (pinfunction "P$29_P$29") (pintype "bidirectional"))
    )
    (net (code "93") (name "unconnected-(U$4-PadP$30)") (class "Default")
      (node (ref "U$4") (pin "P$30") (pinfunction "P$30_P$30") (pintype "bidirectional"))
    )
    (net (code "94") (name "unconnected-(U$4-PadP$31)") (class "Default")
      (node (ref "U$4") (pin "P$31") (pinfunction "P$31_P$31") (pintype "bidirectional"))
    )
    (net (code "95") (name "unconnected-(U$5-Pad5V)") (class "Default")
      (node (ref "U$5") (pin "5V") (pinfunction "5V_5V") (pintype "bidirectional"))
    )
    (net (code "96") (name "unconnected-(U$5-PadP$1)") (class "Default")
      (node (ref "U$5") (pin "P$1") (pinfunction "P$1_P$1") (pintype "bidirectional"))
    )
    (net (code "97") (name "unconnected-(U$5-PadP$6)") (class "Default")
      (node (ref "U$5") (pin "P$6") (pinfunction "P$6_P$6") (pintype "bidirectional"))
    )
    (net (code "98") (name "unconnected-(U$5-PadP$7)") (class "Default")
      (node (ref "U$5") (pin "P$7") (pinfunction "P$7_P$7") (pintype "bidirectional"))
    )
    (net (code "99") (name "unconnected-(U$5-PadP$8)") (class "Default")
      (node (ref "U$5") (pin "P$8") (pinfunction "P$8_P$8") (pintype "bidirectional"))
    )
    (net (code "100") (name "unconnected-(U$5-PadP$10)") (class "Default")
      (node (ref "U$5") (pin "P$10") (pinfunction "P$10_P$10") (pintype "bidirectional"))
    )
    (net (code "101") (name "unconnected-(U$5-PadP$11)") (class "Default")
      (node (ref "U$5") (pin "P$11") (pinfunction "P$11_P$11") (pintype "bidirectional"))
    )
    (net (code "102") (name "unconnected-(U$5-PadP$12)") (class "Default")
      (node (ref "U$5") (pin "P$12") (pinfunction "P$12_P$12") (pintype "bidirectional"))
    )
    (net (code "103") (name "unconnected-(U$5-PadP$13)") (class "Default")
      (node (ref "U$5") (pin "P$13") (pinfunction "P$13_P$13") (pintype "bidirectional"))
    )
    (net (code "104") (name "unconnected-(U$5-PadP$14)") (class "Default")
      (node (ref "U$5") (pin "P$14") (pinfunction "P$14_P$14") (pintype "bidirectional"))
    )
    (net (code "105") (name "unconnected-(U$5-PadP$15)") (class "Default")
      (node (ref "U$5") (pin "P$15") (pinfunction "P$15_P$15") (pintype "bidirectional"))
    )
    (net (code "106") (name "unconnected-(U$5-PadP$18)") (class "Default")
      (node (ref "U$5") (pin "P$18") (pinfunction "P$18_P$18") (pintype "bidirectional"))
    )
    (net (code "107") (name "unconnected-(U$5-PadP$19)") (class "Default")
      (node (ref "U$5") (pin "P$19") (pinfunction "P$19_P$19") (pintype "bidirectional"))
    )
    (net (code "108") (name "unconnected-(U$5-PadP$22)") (class "Default")
      (node (ref "U$5") (pin "P$22") (pinfunction "P$22_P$22") (pintype "bidirectional"))
    )
    (net (code "109") (name "unconnected-(U$5-PadP$23)") (class "Default")
      (node (ref "U$5") (pin "P$23") (pinfunction "P$23_P$23") (pintype "bidirectional"))
    )
    (net (code "110") (name "unconnected-(U$5-PadP$24)") (class "Default")
      (node (ref "U$5") (pin "P$24") (pinfunction "P$24_P$24") (pintype "bidirectional"))
    )
    (net (code "111") (name "unconnected-(U$5-PadP$26)") (class "Default")
      (node (ref "U$5") (pin "P$26") (pinfunction "P$26_P$26") (pintype "bidirectional"))
    )
    (net (code "112") (name "unconnected-(U$5-PadP$27)") (class "Default")
      (node (ref "U$5") (pin "P$27") (pinfunction "P$27_P$27") (pintype "bidirectional"))
    )
    (net (code "113") (name "unconnected-(U$5-PadP$28)") (class "Default")
      (node (ref "U$5") (pin "P$28") (pinfunction "P$28_P$28") (pintype "bidirectional"))
    )
    (net (code "114") (name "unconnected-(U$5-PadP$29)") (class "Default")
      (node (ref "U$5") (pin "P$29") (pinfunction "P$29_P$29") (pintype "bidirectional"))
    )
    (net (code "115") (name "unconnected-(U$5-PadP$30)") (class "Default")
      (node (ref "U$5") (pin "P$30") (pinfunction "P$30_P$30") (pintype "bidirectional"))
    )
    (net (code "116") (name "unconnected-(U$5-PadP$31)") (class "Default")
      (node (ref "U$5") (pin "P$31") (pinfunction "P$31_P$31") (pintype "bidirectional"))
    )
    (net (code "117") (name "unconnected-(U$6-PadP$5)") (class "Default")
      (node (ref "U$6") (pin "P$5") (pinfunction "P$5_P$5") (pintype "bidirectional"))
    )
    (net (code "118") (name "unconnected-(U$6-PadP$7)") (class "Default")
      (node (ref "U$6") (pin "P$7") (pinfunction "P$7_P$7") (pintype "bidirectional"))
    )
    (net (code "119") (name "unconnected-(U$6-PadP$8)") (class "Default")
      (node (ref "U$6") (pin "P$8") (pinfunction "P$8_P$8") (pintype "bidirectional"))
    )
    (net (code "120") (name "unconnected-(U$6-PadP$9)") (class "Default")
      (node (ref "U$6") (pin "P$9") (pinfunction "P$9_P$9") (pintype "bidirectional"))
    )
    (net (code "121") (name "unconnected-(U$6-PadP$10)") (class "Default")
      (node (ref "U$6") (pin "P$10") (pinfunction "P$10_P$10") (pintype "bidirectional"))
    )
    (net (code "122") (name "unconnected-(U$6-PadP$11)") (class "Default")
      (node (ref "U$6") (pin "P$11") (pinfunction "P$11_P$11") (pintype "bidirectional"))
    )
    (net (code "123") (name "unconnected-(U$6-PadP$12)") (class "Default")
      (node (ref "U$6") (pin "P$12") (pinfunction "P$12_P$12") (pintype "bidirectional"))
    )
    (net (code "124") (name "unconnected-(U$6-PadP$13)") (class "Default")
      (node (ref "U$6") (pin "P$13") (pinfunction "P$13_P$13") (pintype "bidirectional"))
    )
    (net (code "125") (name "unconnected-(U$6-PadP$14)") (class "Default")
      (node (ref "U$6") (pin "P$14") (pinfunction "P$14_P$14") (pintype "bidirectional"))
    )
    (net (code "126") (name "unconnected-(U$6-PadP$15)") (class "Default")
      (node (ref "U$6") (pin "P$15") (pinfunction "P$15_P$15") (pintype "bidirectional"))
    )
    (net (code "127") (name "unconnected-(U$6-PadP$16)") (class "Default")
      (node (ref "U$6") (pin "P$16") (pinfunction "P$16_P$16") (pintype "bidirectional"))
    )
    (net (code "128") (name "unconnected-(U$6-PadP$17)") (class "Default")
      (node (ref "U$6") (pin "P$17") (pinfunction "P$17_P$17") (pintype "bidirectional"))
    )
    (net (code "129") (name "unconnected-(U$6-PadP$18)") (class "Default")
      (node (ref "U$6") (pin "P$18") (pinfunction "P$18_P$18") (pintype "bidirectional"))
    )
    (net (code "130") (name "unconnected-(U$6-PadP$19)") (class "Default")
      (node (ref "U$6") (pin "P$19") (pinfunction "P$19_P$19") (pintype "bidirectional"))
    )
    (net (code "131") (name "unconnected-(U$6-PadP$20)") (class "Default")
      (node (ref "U$6") (pin "P$20") (pinfunction "P$20_P$20") (pintype "bidirectional"))
    )
    (net (code "132") (name "unconnected-(U$6-PadP$21)") (class "Default")
      (node (ref "U$6") (pin "P$21") (pinfunction "P$21_P$21") (pintype "bidirectional"))
    )
    (net (code "133") (name "unconnected-(U$6-PadP$22)") (class "Default")
      (node (ref "U$6") (pin "P$22") (pinfunction "P$22_P$22") (pintype "bidirectional"))
    )
    (net (code "134") (name "unconnected-(U$6-PadP$23)") (class "Default")
      (node (ref "U$6") (pin "P$23") (pinfunction "P$23_P$23") (pintype "bidirectional"))
    )
    (net (code "135") (name "unconnected-(U$6-PadP$24)") (class "Default")
      (node (ref "U$6") (pin "P$24") (pinfunction "P$24_P$24") (pintype "bidirectional"))
    )
    (net (code "136") (name "unconnected-(U$6-PadP$26)") (class "Default")
      (node (ref "U$6") (pin "P$26") (pinfunction "P$26_P$26") (pintype "bidirectional"))
    )
    (net (code "137") (name "unconnected-(U$6-PadP$27)") (class "Default")
      (node (ref "U$6") (pin "P$27") (pinfunction "P$27_P$27") (pintype "bidirectional"))
    )
    (net (code "138") (name "unconnected-(U$6-PadP$29)") (class "Default")
      (node (ref "U$6") (pin "P$29") (pinfunction "P$29_P$29") (pintype "bidirectional"))
    )
    (net (code "139") (name "unconnected-(U$6-PadP$30)") (class "Default")
      (node (ref "U$6") (pin "P$30") (pinfunction "P$30_P$30") (pintype "bidirectional"))
    )
    (net (code "140") (name "unconnected-(U$6-PadP$31)") (class "Default")
      (node (ref "U$6") (pin "P$31") (pinfunction "P$31_P$31") (pintype "bidirectional"))
    )
    (net (code "141") (name "unconnected-(U$7-Pad5V)") (class "Default")
      (node (ref "U$7") (pin "5V") (pinfunction "5V_5V") (pintype "bidirectional"))
    )
    (net (code "142") (name "unconnected-(U$7-PadP$1)") (class "Default")
      (node (ref "U$7") (pin "P$1") (pinfunction "P$1_P$1") (pintype "bidirectional"))
    )
    (net (code "143") (name "unconnected-(U$7-PadP$6)") (class "Default")
      (node (ref "U$7") (pin "P$6") (pinfunction "P$6_P$6") (pintype "bidirectional"))
    )
    (net (code "144") (name "unconnected-(U$7-PadP$7)") (class "Default")
      (node (ref "U$7") (pin "P$7") (pinfunction "P$7_P$7") (pintype "bidirectional"))
    )
    (net (code "145") (name "unconnected-(U$7-PadP$8)") (class "Default")
      (node (ref "U$7") (pin "P$8") (pinfunction "P$8_P$8") (pintype "bidirectional"))
    )
    (net (code "146") (name "unconnected-(U$7-PadP$10)") (class "Default")
      (node (ref "U$7") (pin "P$10") (pinfunction "P$10_P$10") (pintype "bidirectional"))
    )
    (net (code "147") (name "unconnected-(U$7-PadP$11)") (class "Default")
      (node (ref "U$7") (pin "P$11") (pinfunction "P$11_P$11") (pintype "bidirectional"))
    )
    (net (code "148") (name "unconnected-(U$7-PadP$12)") (class "Default")
      (node (ref "U$7") (pin "P$12") (pinfunction "P$12_P$12") (pintype "bidirectional"))
    )
    (net (code "149") (name "unconnected-(U$7-PadP$13)") (class "Default")
      (node (ref "U$7") (pin "P$13") (pinfunction "P$13_P$13") (pintype "bidirectional"))
    )
    (net (code "150") (name "unconnected-(U$7-PadP$14)") (class "Default")
      (node (ref "U$7") (pin "P$14") (pinfunction "P$14_P$14") (pintype "bidirectional"))
    )
    (net (code "151") (name "unconnected-(U$7-PadP$15)") (class "Default")
      (node (ref "U$7") (pin "P$15") (pinfunction "P$15_P$15") (pintype "bidirectional"))
    )
    (net (code "152") (name "unconnected-(U$7-PadP$18)") (class "Default")
      (node (ref "U$7") (pin "P$18") (pinfunction "P$18_P$18") (pintype "bidirectional"))
    )
    (net (code "153") (name "unconnected-(U$7-PadP$19)") (class "Default")
      (node (ref "U$7") (pin "P$19") (pinfunction "P$19_P$19") (pintype "bidirectional"))
    )
    (net (code "154") (name "unconnected-(U$7-PadP$22)") (class "Default")
      (node (ref "U$7") (pin "P$22") (pinfunction "P$22_P$22") (pintype "bidirectional"))
    )
    (net (code "155") (name "unconnected-(U$7-PadP$23)") (class "Default")
      (node (ref "U$7") (pin "P$23") (pinfunction "P$23_P$23") (pintype "bidirectional"))
    )
    (net (code "156") (name "unconnected-(U$7-PadP$24)") (class "Default")
      (node (ref "U$7") (pin "P$24") (pinfunction "P$24_P$24") (pintype "bidirectional"))
    )
    (net (code "157") (name "unconnected-(U$7-PadP$26)") (class "Default")
      (node (ref "U$7") (pin "P$26") (pinfunction "P$26_P$26") (pintype "bidirectional"))
    )
    (net (code "158") (name "unconnected-(U$7-PadP$27)") (class "Default")
      (node (ref "U$7") (pin "P$27") (pinfunction "P$27_P$27") (pintype "bidirectional"))
    )
    (net (code "159") (name "unconnected-(U$7-PadP$28)") (class "Default")
      (node (ref "U$7") (pin "P$28") (pinfunction "P$28_P$28") (pintype "bidirectional"))
    )
    (net (code "160") (name "unconnected-(U$7-PadP$29)") (class "Default")
      (node (ref "U$7") (pin "P$29") (pinfunction "P$29_P$29") (pintype "bidirectional"))
    )
    (net (code "161") (name "unconnected-(U$7-PadP$30)") (class "Default")
      (node (ref "U$7") (pin "P$30") (pinfunction "P$30_P$30") (pintype "bidirectional"))
    )
    (net (code "162") (name "unconnected-(U$7-PadP$31)") (class "Default")
      (node (ref "U$7") (pin "P$31") (pinfunction "P$31_P$31") (pintype "bidirectional"))
    )
    (net (code "163") (name "unconnected-(U$8-PadP$5)") (class "Default")
      (node (ref "U$8") (pin "P$5") (pinfunction "P$5_P$5") (pintype "bidirectional"))
    )
    (net (code "164") (name "unconnected-(U$8-PadP$7)") (class "Default")
      (node (ref "U$8") (pin "P$7") (pinfunction "P$7_P$7") (pintype "bidirectional"))
    )
    (net (code "165") (name "unconnected-(U$8-PadP$8)") (class "Default")
      (node (ref "U$8") (pin "P$8") (pinfunction "P$8_P$8") (pintype "bidirectional"))
    )
    (net (code "166") (name "unconnected-(U$8-PadP$9)") (class "Default")
      (node (ref "U$8") (pin "P$9") (pinfunction "P$9_P$9") (pintype "bidirectional"))
    )
    (net (code "167") (name "unconnected-(U$8-PadP$10)") (class "Default")
      (node (ref "U$8") (pin "P$10") (pinfunction "P$10_P$10") (pintype "bidirectional"))
    )
    (net (code "168") (name "unconnected-(U$8-PadP$11)") (class "Default")
      (node (ref "U$8") (pin "P$11") (pinfunction "P$11_P$11") (pintype "bidirectional"))
    )
    (net (code "169") (name "unconnected-(U$8-PadP$12)") (class "Default")
      (node (ref "U$8") (pin "P$12") (pinfunction "P$12_P$12") (pintype "bidirectional"))
    )
    (net (code "170") (name "unconnected-(U$8-PadP$13)") (class "Default")
      (node (ref "U$8") (pin "P$13") (pinfunction "P$13_P$13") (pintype "bidirectional"))
    )
    (net (code "171") (name "unconnected-(U$8-PadP$14)") (class "Default")
      (node (ref "U$8") (pin "P$14") (pinfunction "P$14_P$14") (pintype "bidirectional"))
    )
    (net (code "172") (name "unconnected-(U$8-PadP$15)") (class "Default")
      (node (ref "U$8") (pin "P$15") (pinfunction "P$15_P$15") (pintype "bidirectional"))
    )
    (net (code "173") (name "unconnected-(U$8-PadP$16)") (class "Default")
      (node (ref "U$8") (pin "P$16") (pinfunction "P$16_P$16") (pintype "bidirectional"))
    )
    (net (code "174") (name "unconnected-(U$8-PadP$17)") (class "Default")
      (node (ref "U$8") (pin "P$17") (pinfunction "P$17_P$17") (pintype "bidirectional"))
    )
    (net (code "175") (name "unconnected-(U$8-PadP$18)") (class "Default")
      (node (ref "U$8") (pin "P$18") (pinfunction "P$18_P$18") (pintype "bidirectional"))
    )
    (net (code "176") (name "unconnected-(U$8-PadP$19)") (class "Default")
      (node (ref "U$8") (pin "P$19") (pinfunction "P$19_P$19") (pintype "bidirectional"))
    )
    (net (code "177") (name "unconnected-(U$8-PadP$20)") (class "Default")
      (node (ref "U$8") (pin "P$20") (pinfunction "P$20_P$20") (pintype "bidirectional"))
    )
    (net (code "178") (name "unconnected-(U$8-PadP$21)") (class "Default")
      (node (ref "U$8") (pin "P$21") (pinfunction "P$21_P$21") (pintype "bidirectional"))
    )
    (net (code "179") (name "unconnected-(U$8-PadP$22)") (class "Default")
      (node (ref "U$8") (pin "P$22") (pinfunction "P$22_P$22") (pintype "bidirectional"))
    )
    (net (code "180") (name "unconnected-(U$8-PadP$23)") (class "Default")
      (node (ref "U$8") (pin "P$23") (pinfunction "P$23_P$23") (pintype "bidirectional"))
    )
    (net (code "181") (name "unconnected-(U$8-PadP$24)") (class "Default")
      (node (ref "U$8") (pin "P$24") (pinfunction "P$24_P$24") (pintype "bidirectional"))
    )
    (net (code "182") (name "unconnected-(U$8-PadP$26)") (class "Default")
      (node (ref "U$8") (pin "P$26") (pinfunction "P$26_P$26") (pintype "bidirectional"))
    )
    (net (code "183") (name "unconnected-(U$8-PadP$27)") (class "Default")
      (node (ref "U$8") (pin "P$27") (pinfunction "P$27_P$27") (pintype "bidirectional"))
    )
    (net (code "184") (name "unconnected-(U$8-PadP$29)") (class "Default")
      (node (ref "U$8") (pin "P$29") (pinfunction "P$29_P$29") (pintype "bidirectional"))
    )
    (net (code "185") (name "unconnected-(U$8-PadP$30)") (class "Default")
      (node (ref "U$8") (pin "P$30") (pinfunction "P$30_P$30") (pintype "bidirectional"))
    )
    (net (code "186") (name "unconnected-(U$8-PadP$31)") (class "Default")
      (node (ref "U$8") (pin "P$31") (pinfunction "P$31_P$31") (pintype "bidirectional"))
    )
    (net (code "187") (name "unconnected-(U$9-PadNC)") (class "Default")
      (node (ref "U$9") (pin "NC") (pinfunction "NC_NC") (pintype "bidirectional"))
    )
    (net (code "188") (name "unconnected-(U$9-PadNC1)") (class "Default")
      (node (ref "U$9") (pin "NC1") (pinfunction "NC1_NC1") (pintype "bidirectional"))
    )
  )
)
